# bk-circ3-S.net
KiCad netlist of a schematic drawn in EAGLE
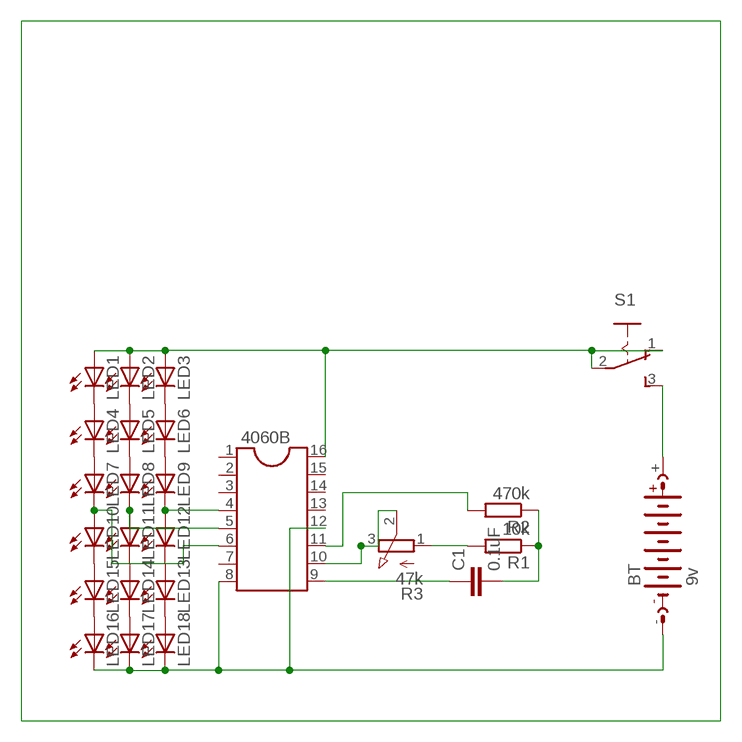
[diagram p0: schematic, sheet 1]

(export (version "E")
  (design (tool "Eeschema 10.0.6"))
  (components
    (comp (ref "4060B")
      (value "DIL16")
      (footprint "eagle-import:DIL16")
      (libsource (lib "eagle-import") (part "DIL16"))
    )
    (comp (ref "BT")
      (value "9v")
      (footprint "eagle-import:AB9V")
      (libsource (lib "eagle-import") (part "AB9V"))
    )
    (comp (ref "C1")
      (value "0.1uF")
      (footprint "eagle-import:C050-030X075")
      (libsource (lib "eagle-import") (part "C-EU050-030X075"))
    )
    (comp (ref "LED1")
      (value "LED3MM")
      (footprint "eagle-import:LED3MM")
      (libsource (lib "eagle-import") (part "LED3MM"))
    )
    (comp (ref "LED2")
      (value "LED3MM")
      (footprint "eagle-import:LED3MM")
      (libsource (lib "eagle-import") (part "LED3MM"))
    )
    (comp (ref "LED3")
      (value "LED3MM")
      (footprint "eagle-import:LED3MM")
      (libsource (lib "eagle-import") (part "LED3MM"))
    )
    (comp (ref "LED4")
      (value "LED3MM")
      (footprint "eagle-import:LED3MM")
      (libsource (lib "eagle-import") (part "LED3MM"))
    )
    (comp (ref "LED5")
      (value "LED3MM")
      (footprint "eagle-import:LED3MM")
      (libsource (lib "eagle-import") (part "LED3MM"))
    )
    (comp (ref "LED6")
      (value "LED3MM")
      (footprint "eagle-import:LED3MM")
      (libsource (lib "eagle-import") (part "LED3MM"))
    )
    (comp (ref "LED7")
      (value "LED3MM")
      (footprint "eagle-import:LED3MM")
      (libsource (lib "eagle-import") (part "LED3MM"))
    )
    (comp (ref "LED8")
      (value "LED3MM")
      (footprint "eagle-import:LED3MM")
      (libsource (lib "eagle-import") (part "LED3MM"))
    )
    (comp (ref "LED9")
      (value "LED3MM")
      (footprint "eagle-import:LED3MM")
      (libsource (lib "eagle-import") (part "LED3MM"))
    )
    (comp (ref "LED10")
      (value "LED3MM")
      (footprint "eagle-import:LED3MM")
      (libsource (lib "eagle-import") (part "LED3MM"))
    )
    (comp (ref "LED11")
      (value "LED3MM")
      (footprint "eagle-import:LED3MM")
      (libsource (lib "eagle-import") (part "LED3MM"))
    )
    (comp (ref "LED12")
      (value "LED3MM")
      (footprint "eagle-import:LED3MM")
      (libsource (lib "eagle-import") (part "LED3MM"))
    )
    (comp (ref "LED13")
      (value "LED3MM")
      (footprint "eagle-import:LED3MM")
      (libsource (lib "eagle-import") (part "LED3MM"))
    )
    (comp (ref "LED14")
      (value "LED3MM")
      (footprint "eagle-import:LED3MM")
      (libsource (lib "eagle-import") (part "LED3MM"))
    )
    (comp (ref "LED15")
      (value "LED3MM")
      (footprint "eagle-import:LED3MM")
      (libsource (lib "eagle-import") (part "LED3MM"))
    )
    (comp (ref "LED16")
      (value "LED3MM")
      (footprint "eagle-import:LED3MM")
      (libsource (lib "eagle-import") (part "LED3MM"))
    )
    (comp (ref "LED17")
      (value "LED3MM")
      (footprint "eagle-import:LED3MM")
      (libsource (lib "eagle-import") (part "LED3MM"))
    )
    (comp (ref "LED18")
      (value "LED3MM")
      (footprint "eagle-import:LED3MM")
      (libsource (lib "eagle-import") (part "LED3MM"))
    )
    (comp (ref "R1")
      (value "10k")
      (footprint "eagle-import:0207_7")
      (libsource (lib "eagle-import") (part "R-EU_0207/7"))
    )
    (comp (ref "R2")
      (value "470k")
      (footprint "eagle-import:0207_7")
      (libsource (lib "eagle-import") (part "R-EU_0207/7"))
    )
    (comp (ref "R3")
      (value "47k")
      (footprint "eagle-import:3RP_1610N")
      (libsource (lib "eagle-import") (part "3RP/1610N"))
    )
    (comp (ref "S1")
      (value "255SB")
      (footprint "eagle-import:255SB")
      (libsource (lib "eagle-import") (part "255SB"))
    )
  )
  (nets
    (net (code "1") (name "Net-(4060B-Pad9)") (class "Default")
      (node (ref "4060B") (pin "9") (pinfunction "9_9") (pintype "passive"))
      (node (ref "C1") (pin "1") (pinfunction "1_1") (pintype "passive"))
    )
    (net (code "2") (name "Net-(4060B-Pad11)") (class "Default")
      (node (ref "4060B") (pin "11") (pinfunction "11_11") (pintype "passive"))
      (node (ref "R2") (pin "2") (pinfunction "2_2") (pintype "passive"))
    )
    (net (code "3") (name "Net-(C1-Pad2)") (class "Default")
      (node (ref "C1") (pin "2") (pinfunction "2_2") (pintype "passive"))
      (node (ref "R1") (pin "1") (pinfunction "1_1") (pintype "passive"))
      (node (ref "R2") (pin "1") (pinfunction "1_1") (pintype "passive"))
    )
    (net (code "4") (name "Net-(LED1-C)") (class "Default")
      (node (ref "LED1") (pin "K") (pinfunction "C_K") (pintype "passive"))
      (node (ref "LED4") (pin "A") (pinfunction "A_A") (pintype "passive"))
    )
    (net (code "5") (name "Net-(LED2-C)") (class "Default")
      (node (ref "LED2") (pin "K") (pinfunction "C_K") (pintype "passive"))
      (node (ref "LED5") (pin "A") (pinfunction "A_A") (pintype "passive"))
    )
    (net (code "6") (name "Net-(LED3-C)") (class "Default")
      (node (ref "LED3") (pin "K") (pinfunction "C_K") (pintype "passive"))
      (node (ref "LED6") (pin "A") (pinfunction "A_A") (pintype "passive"))
    )
    (net (code "7") (name "Net-(LED4-C)") (class "Default")
      (node (ref "LED4") (pin "K") (pinfunction "C_K") (pintype "passive"))
      (node (ref "LED7") (pin "A") (pinfunction "A_A") (pintype "passive"))
    )
    (net (code "8") (name "Net-(LED5-C)") (class "Default")
      (node (ref "LED5") (pin "K") (pinfunction "C_K") (pintype "passive"))
      (node (ref "LED8") (pin "A") (pinfunction "A_A") (pintype "passive"))
    )
    (net (code "9") (name "Net-(LED6-C)") (class "Default")
      (node (ref "LED6") (pin "K") (pinfunction "C_K") (pintype "passive"))
      (node (ref "LED9") (pin "A") (pinfunction "A_A") (pintype "passive"))
    )
    (net (code "10") (name "Net-(LED7-C)") (class "Default")
      (node (ref "4060B") (pin "6") (pinfunction "6_6") (pintype "passive"))
      (node (ref "LED10") (pin "A") (pinfunction "A_A") (pintype "passive"))
      (node (ref "LED7") (pin "K") (pinfunction "C_K") (pintype "passive"))
    )
    (net (code "11") (name "Net-(LED8-C)") (class "Default")
      (node (ref "4060B") (pin "5") (pinfunction "5_5") (pintype "passive"))
      (node (ref "LED11") (pin "A") (pinfunction "A_A") (pintype "passive"))
      (node (ref "LED8") (pin "K") (pinfunction "C_K") (pintype "passive"))
    )
    (net (code "12") (name "Net-(LED9-C)") (class "Default")
      (node (ref "4060B") (pin "4") (pinfunction "4_4") (pintype "passive"))
      (node (ref "LED12") (pin "A") (pinfunction "A_A") (pintype "passive"))
      (node (ref "LED9") (pin "K") (pinfunction "C_K") (pintype "passive"))
    )
    (net (code "13") (name "Net-(LED10-C)") (class "Default")
      (node (ref "LED10") (pin "K") (pinfunction "C_K") (pintype "passive"))
      (node (ref "LED15") (pin "A") (pinfunction "A_A") (pintype "passive"))
    )
    (net (code "14") (name "Net-(LED11-C)") (class "Default")
      (node (ref "LED11") (pin "K") (pinfunction "C_K") (pintype "passive"))
      (node (ref "LED14") (pin "A") (pinfunction "A_A") (pintype "passive"))
    )
    (net (code "15") (name "Net-(LED12-C)") (class "Default")
      (node (ref "LED12") (pin "K") (pinfunction "C_K") (pintype "passive"))
      (node (ref "LED13") (pin "A") (pinfunction "A_A") (pintype "passive"))
    )
    (net (code "16") (name "Net-(LED13-C)") (class "Default")
      (node (ref "LED13") (pin "K") (pinfunction "C_K") (pintype "passive"))
      (node (ref "LED18") (pin "A") (pinfunction "A_A") (pintype "passive"))
    )
    (net (code "17") (name "Net-(LED14-C)") (class "Default")
      (node (ref "LED14") (pin "K") (pinfunction "C_K") (pintype "passive"))
      (node (ref "LED17") (pin "A") (pinfunction "A_A") (pintype "passive"))
    )
    (net (code "18") (name "Net-(LED15-C)") (class "Default")
      (node (ref "LED15") (pin "K") (pinfunction "C_K") (pintype "passive"))
      (node (ref "LED16") (pin "A") (pinfunction "A_A") (pintype "passive"))
    )
    (net (code "19") (name "Net-(LED16-C)") (class "Default")
      (node (ref "4060B") (pin "12") (pinfunction "12_12") (pintype "passive"))
      (node (ref "4060B") (pin "8") (pinfunction "8_8") (pintype "passive"))
      (node (ref "BT") (pin "-") (pinfunction "-_-") (pintype "passive"))
      (node (ref "LED16") (pin "K") (pinfunction "C_K") (pintype "passive"))
      (node (ref "LED17") (pin "K") (pinfunction "C_K") (pintype "passive"))
      (node (ref "LED18") (pin "K") (pinfunction "C_K") (pintype "passive"))
    )
    (net (code "20") (name "Net-(R3-A)") (class "Default")
      (node (ref "R1") (pin "2") (pinfunction "2_2") (pintype "passive"))
      (node (ref "R3") (pin "1") (pinfunction "A_1") (pintype "passive"))
    )
    (net (code "21") (name "Net-(R3-E)") (class "Default")
      (node (ref "4060B") (pin "10") (pinfunction "10_10") (pintype "passive"))
      (node (ref "R3") (pin "2") (pinfunction "S_2") (pintype "passive"))
      (node (ref "R3") (pin "3") (pinfunction "E_3") (pintype "passive"))
    )
    (net (code "22") (name "Net-(S1-O)") (class "Default")
      (node (ref "4060B") (pin "16") (pinfunction "16_16") (pintype "passive"))
      (node (ref "LED1") (pin "A") (pinfunction "A_A") (pintype "passive"))
      (node (ref "LED2") (pin "A") (pinfunction "A_A") (pintype "passive"))
      (node (ref "LED3") (pin "A") (pinfunction "A_A") (pintype "passive"))
      (node (ref "S1") (pin "1") (pinfunction "O_1") (pintype "passive"))
      (node (ref "S1") (pin "2") (pinfunction "P_2") (pintype "passive"))
    )
    (net (code "23") (name "Net-(S1-S)") (class "Default")
      (node (ref "BT") (pin "+") (pinfunction "+_+") (pintype "passive"))
      (node (ref "S1") (pin "3") (pinfunction "S_3") (pintype "passive"))
    )
    (net (code "24") (name "unconnected-(4060B-Pad1)") (class "Default")
      (node (ref "4060B") (pin "1") (pinfunction "1_1") (pintype "passive"))
    )
    (net (code "25") (name "unconnected-(4060B-Pad2)") (class "Default")
      (node (ref "4060B") (pin "2") (pinfunction "2_2") (pintype "passive"))
    )
    (net (code "26") (name "unconnected-(4060B-Pad3)") (class "Default")
      (node (ref "4060B") (pin "3") (pinfunction "3_3") (pintype "passive"))
    )
    (net (code "27") (name "unconnected-(4060B-Pad7)") (class "Default")
      (node (ref "4060B") (pin "7") (pinfunction "7_7") (pintype "passive"))
    )
    (net (code "28") (name "unconnected-(4060B-Pad13)") (class "Default")
      (node (ref "4060B") (pin "13") (pinfunction "13_13") (pintype "passive"))
    )
    (net (code "29") (name "unconnected-(4060B-Pad14)") (class "Default")
      (node (ref "4060B") (pin "14") (pinfunction "14_14") (pintype "passive"))
    )
    (net (code "30") (name "unconnected-(4060B-Pad15)") (class "Default")
      (node (ref "4060B") (pin "15") (pinfunction "15_15") (pintype "passive"))
    )
  )
)
